# Dcdc_12V0_-16V5.net
KiCad netlist of a schematic drawn in Altium Designer
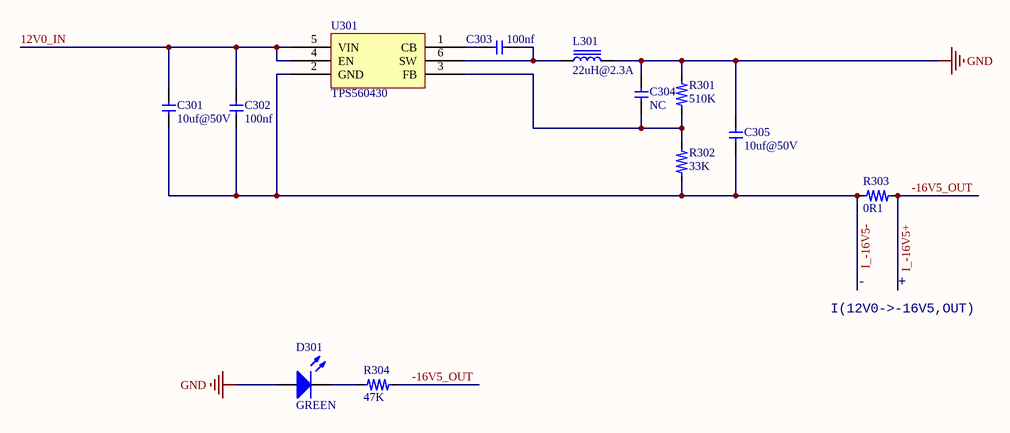
[diagram p0: Dcdc.12V0.-16V5.SchDoc]

(export (version "E")
  (design (tool "Eeschema 10.0.6"))
  (components
    (comp (ref "C301")
      (value "10uf@50V")
      (footprint "C1210")
      (fields (field (name "Comment") "Cap"))
      (libsource (lib "carrot_lib") (part "Cap"))
    )
    (comp (ref "C302")
      (value "100nf")
      (footprint "C0603")
      (fields (field (name "Comment") "Cap"))
      (libsource (lib "carrot_lib") (part "Cap"))
    )
    (comp (ref "C303")
      (value "100nf")
      (footprint "C0603")
      (fields (field (name "Comment") "Cap"))
      (libsource (lib "carrot_lib") (part "Cap"))
    )
    (comp (ref "C304")
      (value "NC")
      (footprint "C0603")
      (fields (field (name "Comment") "Cap"))
      (libsource (lib "carrot_lib") (part "Cap"))
    )
    (comp (ref "C305")
      (value "10uf@50V")
      (footprint "C1210")
      (fields (field (name "Comment") "Cap"))
      (libsource (lib "carrot_lib") (part "Cap"))
    )
    (comp (ref "D301")
      (value "GREEN")
      (footprint "LED0603")
      (fields (field (name "Comment") "LED"))
      (libsource (lib "carrot_lib") (part "LED"))
    )
    (comp (ref "L301")
      (value "22uH@2.3A")
      (footprint "L06063")
      (description "Magnetic-Core Inductor")
      (fields (field (name "Comment") "Inductor Iron"))
      (libsource (lib "carrot_lib") (part "Inductor Iron"))
    )
    (comp (ref "R301")
      (value "510K")
      (footprint "R0603")
      (description "电阻")
      (fields (field (name "Comment") "Res"))
      (libsource (lib "carrot_lib") (part "Res"))
    )
    (comp (ref "R302")
      (value "33K")
      (footprint "R0603")
      (description "电阻")
      (fields (field (name "Comment") "Res"))
      (libsource (lib "carrot_lib") (part "Res"))
    )
    (comp (ref "R303")
      (value "0R1")
      (footprint "R1206")
      (description "电阻")
      (fields (field (name "Comment") "Res"))
      (libsource (lib "carrot_lib") (part "Res"))
    )
    (comp (ref "R304")
      (value "47K")
      (footprint "R0603")
      (description "电阻")
      (fields (field (name "Comment") "Res"))
      (libsource (lib "carrot_lib") (part "Res"))
    )
    (comp (ref "U301")
      (value "TPS560430")
      (footprint "TPS560430-SOT23-6")
      (description "TPS560430 SIMPLE SWITCHER® 4-V to 36-V, 600-mA Synchronous Step-Down Converter")
      (libsource (lib "carrot_lib") (part "TPS560430"))
    )
  )
  (nets
    (net (code "1") (name "/-16V5_OUT") (class "Default")
      (node (ref "R303") (pin "1") (pinfunction "1_1") (pintype "passive"))
      (node (ref "R304") (pin "1") (pinfunction "1_1") (pintype "passive"))
    )
    (net (code "2") (name "/12V0_IN") (class "Default")
      (node (ref "C301") (pin "2") (pinfunction "2_2") (pintype "passive"))
      (node (ref "C302") (pin "2") (pinfunction "2_2") (pintype "passive"))
      (node (ref "U301") (pin "4") (pinfunction "EN_4") (pintype "passive"))
      (node (ref "U301") (pin "5") (pinfunction "VIN_5") (pintype "passive"))
    )
    (net (code "3") (name "/I_-16V5-") (class "Default")
      (node (ref "C301") (pin "1") (pinfunction "1_1") (pintype "passive"))
      (node (ref "C302") (pin "1") (pinfunction "1_1") (pintype "passive"))
      (node (ref "C305") (pin "1") (pinfunction "1_1") (pintype "passive"))
      (node (ref "R302") (pin "1") (pinfunction "1_1") (pintype "passive"))
      (node (ref "R303") (pin "2") (pinfunction "2_2") (pintype "passive"))
      (node (ref "U301") (pin "2") (pinfunction "GND_2") (pintype "passive"))
    )
    (net (code "4") (name "GND") (class "Default")
      (node (ref "C304") (pin "1") (pinfunction "1_1") (pintype "passive"))
      (node (ref "C305") (pin "2") (pinfunction "2_2") (pintype "passive"))
      (node (ref "D301") (pin "1") (pinfunction "A_1") (pintype "passive"))
      (node (ref "L301") (pin "2") (pinfunction "2_2") (pintype "passive"))
      (node (ref "R301") (pin "2") (pinfunction "2_2") (pintype "passive"))
    )
    (net (code "5") (name "Net-(D301-K)") (class "Default")
      (node (ref "D301") (pin "2") (pinfunction "K_2") (pintype "passive"))
      (node (ref "R304") (pin "2") (pinfunction "2_2") (pintype "passive"))
    )
    (net (code "6") (name "Net-(U301-CB)") (class "Default")
      (node (ref "C303") (pin "2") (pinfunction "2_2") (pintype "passive"))
      (node (ref "U301") (pin "1") (pinfunction "CB_1") (pintype "passive"))
    )
    (net (code "7") (name "Net-(U301-FB)") (class "Default")
      (node (ref "C304") (pin "2") (pinfunction "2_2") (pintype "passive"))
      (node (ref "R301") (pin "1") (pinfunction "1_1") (pintype "passive"))
      (node (ref "R302") (pin "2") (pinfunction "2_2") (pintype "passive"))
      (node (ref "U301") (pin "3") (pinfunction "FB_3") (pintype "passive"))
    )
    (net (code "8") (name "Net-(U301-SW)") (class "Default")
      (node (ref "C303") (pin "1") (pinfunction "1_1") (pintype "passive"))
      (node (ref "L301") (pin "1") (pinfunction "1_1") (pintype "passive"))
      (node (ref "U301") (pin "6") (pinfunction "SW_6") (pintype "passive"))
    )
  )
)
